# FMC_Power_Module.net
KiCad netlist of a schematic drawn in Altium Designer
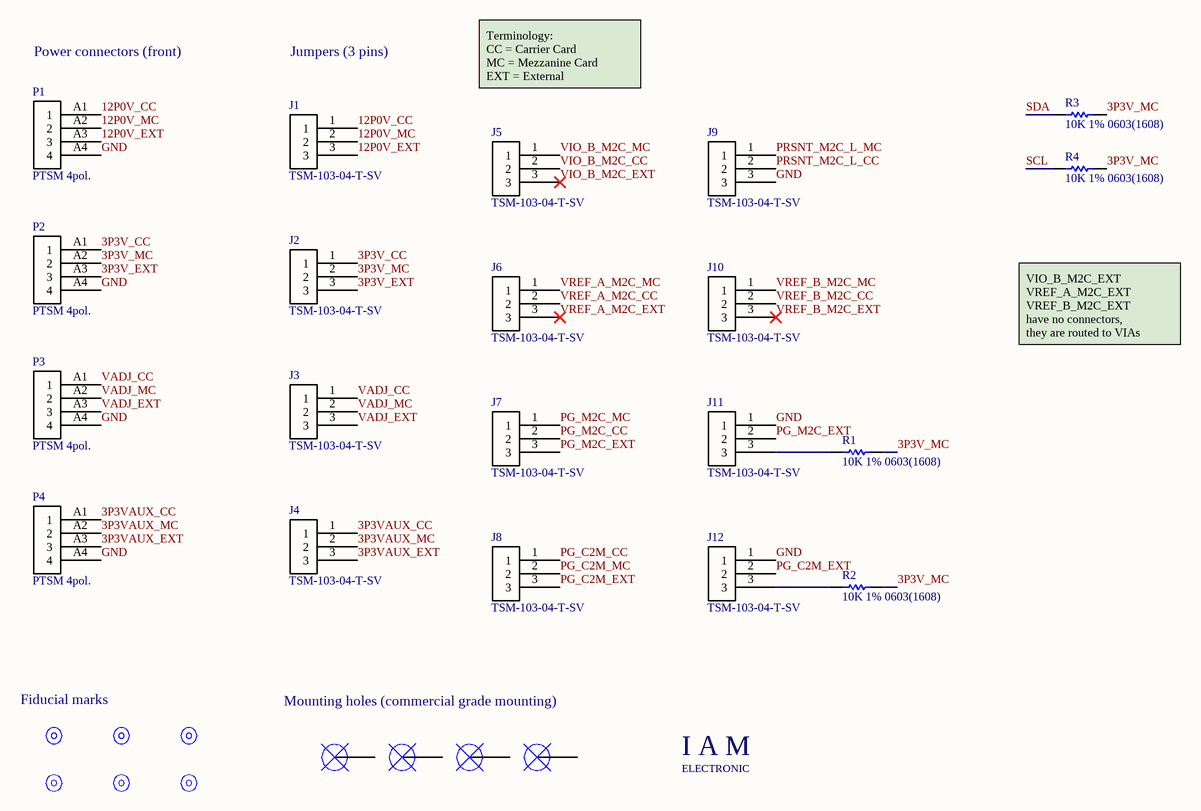
[diagram p0: FMC_Power_Module.SchDoc]

(export (version "E")
  (design (tool "Eeschema 10.0.6"))
  (components
    (comp (ref "FM1")
      (value "1mm")
      (footprint "FIDUCIAL_MARK_ROUND_RING")
      (description "Fiducial mark, width 1mm, clearance 3mm")
      (libsource (lib "VITA_57_FMC") (part "Fiducial_Mark"))
    )
    (comp (ref "FM2")
      (value "1mm")
      (footprint "FIDUCIAL_MARK_ROUND_RING")
      (description "Fiducial mark, width 1mm, clearance 3mm")
      (libsource (lib "VITA_57_FMC") (part "Fiducial_Mark"))
    )
    (comp (ref "FM3")
      (value "1mm")
      (footprint "FIDUCIAL_MARK_ROUND_RING")
      (description "Fiducial mark, width 1mm, clearance 3mm")
      (libsource (lib "VITA_57_FMC") (part "Fiducial_Mark"))
    )
    (comp (ref "FM4")
      (value "1mm")
      (footprint "FIDUCIAL_MARK_ROUND_RING")
      (description "Fiducial mark, width 1mm, clearance 3mm")
      (libsource (lib "VITA_57_FMC") (part "Fiducial_Mark"))
    )
    (comp (ref "FM5")
      (value "1mm")
      (footprint "FIDUCIAL_MARK_ROUND_RING")
      (description "Fiducial mark, width 1mm, clearance 3mm")
      (libsource (lib "VITA_57_FMC") (part "Fiducial_Mark"))
    )
    (comp (ref "FM6")
      (value "1mm")
      (footprint "FIDUCIAL_MARK_ROUND_RING")
      (description "Fiducial mark, width 1mm, clearance 3mm")
      (libsource (lib "VITA_57_FMC") (part "Fiducial_Mark"))
    )
    (comp (ref "J1")
      (value "TSM-103-04-T-SV")
      (footprint "TSM-103-04-T-SV")
      (description ".100\" (2.54 mm) pitch 3 pin header, 0.27\" (6.86 mm) total height, SMT")
      (fields (field (name "MANUFACTURER") "Samtec"))
      (libsource (lib "SMTC-TSM") (part "TSM-103-04-T-SV"))
    )
    (comp (ref "J2")
      (value "TSM-103-04-T-SV")
      (footprint "TSM-103-04-T-SV")
      (description ".100\" (2.54 mm) pitch 3 pin header, 0.27\" (6.86 mm) total height, SMT")
      (fields (field (name "MANUFACTURER") "Samtec"))
      (libsource (lib "SMTC-TSM") (part "TSM-103-04-T-SV"))
    )
    (comp (ref "J3")
      (value "TSM-103-04-T-SV")
      (footprint "TSM-103-04-T-SV")
      (description ".100\" (2.54 mm) pitch 3 pin header, 0.27\" (6.86 mm) total height, SMT")
      (fields (field (name "MANUFACTURER") "Samtec"))
      (libsource (lib "SMTC-TSM") (part "TSM-103-04-T-SV"))
    )
    (comp (ref "J4")
      (value "TSM-103-04-T-SV")
      (footprint "TSM-103-04-T-SV")
      (description ".100\" (2.54 mm) pitch 3 pin header, 0.27\" (6.86 mm) total height, SMT")
      (fields (field (name "MANUFACTURER") "Samtec"))
      (libsource (lib "SMTC-TSM") (part "TSM-103-04-T-SV"))
    )
    (comp (ref "J5")
      (value "TSM-103-04-T-SV")
      (footprint "TSM-103-04-T-SV")
      (description ".100\" (2.54 mm) pitch 3 pin header, 0.27\" (6.86 mm) total height, SMT")
      (fields (field (name "MANUFACTURER") "Samtec"))
      (libsource (lib "SMTC-TSM") (part "TSM-103-04-T-SV"))
    )
    (comp (ref "J6")
      (value "TSM-103-04-T-SV")
      (footprint "TSM-103-04-T-SV")
      (description ".100\" (2.54 mm) pitch 3 pin header, 0.27\" (6.86 mm) total height, SMT")
      (fields (field (name "MANUFACTURER") "Samtec"))
      (libsource (lib "SMTC-TSM") (part "TSM-103-04-T-SV"))
    )
    (comp (ref "J7")
      (value "TSM-103-04-T-SV")
      (footprint "TSM-103-04-T-SV")
      (description ".100\" (2.54 mm) pitch 3 pin header, 0.27\" (6.86 mm) total height, SMT")
      (fields (field (name "MANUFACTURER") "Samtec"))
      (libsource (lib "SMTC-TSM") (part "TSM-103-04-T-SV"))
    )
    (comp (ref "J8")
      (value "TSM-103-04-T-SV")
      (footprint "TSM-103-04-T-SV")
      (description ".100\" (2.54 mm) pitch 3 pin header, 0.27\" (6.86 mm) total height, SMT")
      (fields (field (name "MANUFACTURER") "Samtec"))
      (libsource (lib "SMTC-TSM") (part "TSM-103-04-T-SV"))
    )
    (comp (ref "J9")
      (value "TSM-103-04-T-SV")
      (footprint "TSM-103-04-T-SV")
      (description ".100\" (2.54 mm) pitch 3 pin header, 0.27\" (6.86 mm) total height, SMT")
      (fields (field (name "MANUFACTURER") "Samtec"))
      (libsource (lib "SMTC-TSM") (part "TSM-103-04-T-SV"))
    )
    (comp (ref "J10")
      (value "TSM-103-04-T-SV")
      (footprint "TSM-103-04-T-SV")
      (description ".100\" (2.54 mm) pitch 3 pin header, 0.27\" (6.86 mm) total height, SMT")
      (fields (field (name "MANUFACTURER") "Samtec"))
      (libsource (lib "SMTC-TSM") (part "TSM-103-04-T-SV"))
    )
    (comp (ref "J11")
      (value "TSM-103-04-T-SV")
      (footprint "TSM-103-04-T-SV")
      (description ".100\" (2.54 mm) pitch 3 pin header, 0.27\" (6.86 mm) total height, SMT")
      (fields (field (name "MANUFACTURER") "Samtec"))
      (libsource (lib "SMTC-TSM") (part "TSM-103-04-T-SV"))
    )
    (comp (ref "J12")
      (value "TSM-103-04-T-SV")
      (footprint "TSM-103-04-T-SV")
      (description ".100\" (2.54 mm) pitch 3 pin header, 0.27\" (6.86 mm) total height, SMT")
      (fields (field (name "MANUFACTURER") "Samtec"))
      (libsource (lib "SMTC-TSM") (part "TSM-103-04-T-SV"))
    )
    (comp (ref "MH1")
      (value "2.2mm")
      (footprint "Mounting_Hole_2.2mm")
      (description "Mounting hole, hole size 2.2mm")
      (libsource (lib "VITA_57_FMC") (part "Mounting_Hole_2.2mm"))
    )
    (comp (ref "MH2")
      (value "2.2mm")
      (footprint "Mounting_Hole_2.2mm")
      (description "Mounting hole, hole size 2.2mm")
      (libsource (lib "VITA_57_FMC") (part "Mounting_Hole_2.2mm"))
    )
    (comp (ref "MH3")
      (value "2.7mm")
      (footprint "Mounting_Hole_Plated_2.7mm-COVERED")
      (description "Mounting hole, hole size 2.7mm")
      (libsource (lib "VITA_57_FMC") (part "Mounting_Hole_2.7mm"))
    )
    (comp (ref "MH4")
      (value "2.7mm")
      (footprint "Mounting_Hole_Plated_2.7mm-COVERED")
      (description "Mounting hole, hole size 2.7mm")
      (libsource (lib "VITA_57_FMC") (part "Mounting_Hole_2.7mm"))
    )
    (comp (ref "P1")
      (value "PTSM 4pol.")
      (footprint "PTSM-4pol")
      (description "Phoenix Contact PTSM SMT connector")
      (fields (field (name "MANUFACTURER") "Phoenix Contact") (field (name "PART") "1814650"))
      (libsource (lib "PC-PTSM") (part "PC-PTSM-4pol"))
    )
    (comp (ref "P2")
      (value "PTSM 4pol.")
      (footprint "PTSM-4pol")
      (description "Phoenix Contact PTSM SMT connector")
      (fields (field (name "MANUFACTURER") "Phoenix Contact") (field (name "PART") "1814650"))
      (libsource (lib "PC-PTSM") (part "PC-PTSM-4pol"))
    )
    (comp (ref "P3")
      (value "PTSM 4pol.")
      (footprint "PTSM-4pol")
      (description "Phoenix Contact PTSM SMT connector")
      (fields (field (name "MANUFACTURER") "Phoenix Contact") (field (name "PART") "1814650"))
      (libsource (lib "PC-PTSM") (part "PC-PTSM-4pol"))
    )
    (comp (ref "P4")
      (value "PTSM 4pol.")
      (footprint "PTSM-4pol")
      (description "Phoenix Contact PTSM SMT connector")
      (fields (field (name "MANUFACTURER") "Phoenix Contact") (field (name "PART") "1814650"))
      (libsource (lib "PC-PTSM") (part "PC-PTSM-4pol"))
    )
    (comp (ref "R1")
      (value "10K 1% 0603(1608)")
      (footprint "RESC0603(1608)_N")
      (description "10K 0603 (1608 Metric)  SMD")
      (fields (field (name "POWER") "0.1 W") (field (name "TOLERANCE") "1 %"))
      (libsource (lib "Altium Content Vault") (part "RES"))
    )
    (comp (ref "R2")
      (value "10K 1% 0603(1608)")
      (footprint "RESC0603(1608)_N")
      (description "10K 0603 (1608 Metric)  SMD")
      (fields (field (name "POWER") "0.1 W") (field (name "TOLERANCE") "1 %"))
      (libsource (lib "Altium Content Vault") (part "RES"))
    )
    (comp (ref "R3")
      (value "10K 1% 0603(1608)")
      (footprint "RESC0603(1608)_N")
      (description "10K 0603 (1608 Metric)  SMD")
      (fields (field (name "POWER") "0.1 W") (field (name "TOLERANCE") "1 %"))
      (libsource (lib "Altium Content Vault") (part "RES"))
    )
    (comp (ref "R4")
      (value "10K 1% 0603(1608)")
      (footprint "RESC0603(1608)_N")
      (description "10K 0603 (1608 Metric)  SMD")
      (fields (field (name "POWER") "0.1 W") (field (name "TOLERANCE") "1 %"))
      (libsource (lib "Altium Content Vault") (part "RES"))
    )
    (comp (ref "STR1")
      (value "IAM LOGO")
      (footprint "IAM LOGO - LARGE - WWW")
      (description "I A M E L E C T R O N I C - Logo")
      (fields (field (name "MANUFACTURER") "IAM ELECTRONIC") (field (name "PART") "Logo"))
      (libsource (lib "IAM_LOGOS") (part "IAM_LOGO"))
    )
  )
  (nets
    (net (code "1") (name "/3P3VAUX_CC") (class "Default")
      (node (ref "J4") (pin "1") (pinfunction "1_1") (pintype "passive"))
      (node (ref "P4") (pin "A1") (pinfunction "1_A1") (pintype "passive"))
    )
    (net (code "2") (name "/3P3VAUX_EXT") (class "Default")
      (node (ref "J4") (pin "3") (pinfunction "3_3") (pintype "passive"))
      (node (ref "P4") (pin "A3") (pinfunction "3_A3") (pintype "passive"))
    )
    (net (code "3") (name "/3P3VAUX_MC") (class "Default")
      (node (ref "J4") (pin "2") (pinfunction "2_2") (pintype "passive"))
      (node (ref "P4") (pin "A2") (pinfunction "2_A2") (pintype "passive"))
    )
    (net (code "4") (name "/3P3V_CC") (class "Default")
      (node (ref "J2") (pin "1") (pinfunction "1_1") (pintype "passive"))
      (node (ref "P2") (pin "A1") (pinfunction "1_A1") (pintype "passive"))
    )
    (net (code "5") (name "/3P3V_EXT") (class "Default")
      (node (ref "J2") (pin "3") (pinfunction "3_3") (pintype "passive"))
      (node (ref "P2") (pin "A3") (pinfunction "3_A3") (pintype "passive"))
    )
    (net (code "6") (name "/3P3V_MC") (class "Default")
      (node (ref "J2") (pin "2") (pinfunction "2_2") (pintype "passive"))
      (node (ref "P2") (pin "A2") (pinfunction "2_A2") (pintype "passive"))
      (node (ref "R1") (pin "2") (pinfunction "2_2") (pintype "passive"))
      (node (ref "R2") (pin "2") (pinfunction "2_2") (pintype "passive"))
      (node (ref "R3") (pin "2") (pinfunction "2_2") (pintype "passive"))
      (node (ref "R4") (pin "2") (pinfunction "2_2") (pintype "passive"))
    )
    (net (code "7") (name "/12P0V_CC") (class "Default")
      (node (ref "J1") (pin "1") (pinfunction "1_1") (pintype "passive"))
      (node (ref "P1") (pin "A1") (pinfunction "1_A1") (pintype "passive"))
    )
    (net (code "8") (name "/12P0V_EXT") (class "Default")
      (node (ref "J1") (pin "3") (pinfunction "3_3") (pintype "passive"))
      (node (ref "P1") (pin "A3") (pinfunction "3_A3") (pintype "passive"))
    )
    (net (code "9") (name "/12P0V_MC") (class "Default")
      (node (ref "J1") (pin "2") (pinfunction "2_2") (pintype "passive"))
      (node (ref "P1") (pin "A2") (pinfunction "2_A2") (pintype "passive"))
    )
    (net (code "10") (name "/GND") (class "Default")
      (node (ref "J11") (pin "1") (pinfunction "1_1") (pintype "passive"))
      (node (ref "J12") (pin "1") (pinfunction "1_1") (pintype "passive"))
      (node (ref "J9") (pin "3") (pinfunction "3_3") (pintype "passive"))
      (node (ref "P1") (pin "A4") (pinfunction "4_A4") (pintype "passive"))
      (node (ref "P2") (pin "A4") (pinfunction "4_A4") (pintype "passive"))
      (node (ref "P3") (pin "A4") (pinfunction "4_A4") (pintype "passive"))
      (node (ref "P4") (pin "A4") (pinfunction "4_A4") (pintype "passive"))
    )
    (net (code "11") (name "/PG_C2M_CC") (class "Default")
      (node (ref "J8") (pin "1") (pinfunction "1_1") (pintype "passive"))
    )
    (net (code "12") (name "/PG_C2M_EXT") (class "Default")
      (node (ref "J12") (pin "2") (pinfunction "2_2") (pintype "passive"))
      (node (ref "J8") (pin "3") (pinfunction "3_3") (pintype "passive"))
    )
    (net (code "13") (name "/PG_C2M_MC") (class "Default")
      (node (ref "J8") (pin "2") (pinfunction "2_2") (pintype "passive"))
    )
    (net (code "14") (name "/PG_M2C_CC") (class "Default")
      (node (ref "J7") (pin "2") (pinfunction "2_2") (pintype "passive"))
    )
    (net (code "15") (name "/PG_M2C_EXT") (class "Default")
      (node (ref "J11") (pin "2") (pinfunction "2_2") (pintype "passive"))
      (node (ref "J7") (pin "3") (pinfunction "3_3") (pintype "passive"))
    )
    (net (code "16") (name "/PG_M2C_MC") (class "Default")
      (node (ref "J7") (pin "1") (pinfunction "1_1") (pintype "passive"))
    )
    (net (code "17") (name "/PRSNT_M2C_L_CC") (class "Default")
      (node (ref "J9") (pin "2") (pinfunction "2_2") (pintype "passive"))
    )
    (net (code "18") (name "/PRSNT_M2C_L_MC") (class "Default")
      (node (ref "J9") (pin "1") (pinfunction "1_1") (pintype "passive"))
    )
    (net (code "19") (name "/SCL") (class "Default")
      (node (ref "R4") (pin "1") (pinfunction "1_1") (pintype "passive"))
    )
    (net (code "20") (name "/SDA") (class "Default")
      (node (ref "R3") (pin "1") (pinfunction "1_1") (pintype "passive"))
    )
    (net (code "21") (name "/VADJ_CC") (class "Default")
      (node (ref "J3") (pin "1") (pinfunction "1_1") (pintype "passive"))
      (node (ref "P3") (pin "A1") (pinfunction "1_A1") (pintype "passive"))
    )
    (net (code "22") (name "/VADJ_EXT") (class "Default")
      (node (ref "J3") (pin "3") (pinfunction "3_3") (pintype "passive"))
      (node (ref "P3") (pin "A3") (pinfunction "3_A3") (pintype "passive"))
    )
    (net (code "23") (name "/VADJ_MC") (class "Default")
      (node (ref "J3") (pin "2") (pinfunction "2_2") (pintype "passive"))
      (node (ref "P3") (pin "A2") (pinfunction "2_A2") (pintype "passive"))
    )
    (net (code "24") (name "/VIO_B_M2C_CC") (class "Default")
      (node (ref "J5") (pin "2") (pinfunction "2_2") (pintype "passive"))
    )
    (net (code "25") (name "/VIO_B_M2C_EXT") (class "Default")
      (node (ref "J5") (pin "3") (pinfunction "3_3") (pintype "passive+no_connect"))
    )
    (net (code "26") (name "/VIO_B_M2C_MC") (class "Default")
      (node (ref "J5") (pin "1") (pinfunction "1_1") (pintype "passive"))
    )
    (net (code "27") (name "/VREF_A_M2C_CC") (class "Default")
      (node (ref "J6") (pin "2") (pinfunction "2_2") (pintype "passive"))
    )
    (net (code "28") (name "/VREF_A_M2C_EXT") (class "Default")
      (node (ref "J6") (pin "3") (pinfunction "3_3") (pintype "passive+no_connect"))
    )
    (net (code "29") (name "/VREF_A_M2C_MC") (class "Default")
      (node (ref "J6") (pin "1") (pinfunction "1_1") (pintype "passive"))
    )
    (net (code "30") (name "/VREF_B_M2C_CC") (class "Default")
      (node (ref "J10") (pin "2") (pinfunction "2_2") (pintype "passive"))
    )
    (net (code "31") (name "/VREF_B_M2C_EXT") (class "Default")
      (node (ref "J10") (pin "3") (pinfunction "3_3") (pintype "passive+no_connect"))
    )
    (net (code "32") (name "/VREF_B_M2C_MC") (class "Default")
      (node (ref "J10") (pin "1") (pinfunction "1_1") (pintype "passive"))
    )
    (net (code "33") (name "Net-(J11-Pad3)") (class "Default")
      (node (ref "J11") (pin "3") (pinfunction "3_3") (pintype "passive"))
      (node (ref "R1") (pin "1") (pinfunction "1_1") (pintype "passive"))
    )
    (net (code "34") (name "Net-(J12-Pad3)") (class "Default")
      (node (ref "J12") (pin "3") (pinfunction "3_3") (pintype "passive"))
      (node (ref "R2") (pin "1") (pinfunction "1_1") (pintype "passive"))
    )
    (net (code "35") (name "unconnected-(FM1-PadFD0)") (class "Default")
      (node (ref "FM1") (pin "FD0") (pinfunction "FD0_FD0") (pintype "passive"))
    )
    (net (code "36") (name "unconnected-(FM2-PadFD0)") (class "Default")
      (node (ref "FM2") (pin "FD0") (pinfunction "FD0_FD0") (pintype "passive"))
    )
    (net (code "37") (name "unconnected-(FM3-PadFD0)") (class "Default")
      (node (ref "FM3") (pin "FD0") (pinfunction "FD0_FD0") (pintype "passive"))
    )
    (net (code "38") (name "unconnected-(FM4-PadFD0)") (class "Default")
      (node (ref "FM4") (pin "FD0") (pinfunction "FD0_FD0") (pintype "passive"))
    )
    (net (code "39") (name "unconnected-(FM5-PadFD0)") (class "Default")
      (node (ref "FM5") (pin "FD0") (pinfunction "FD0_FD0") (pintype "passive"))
    )
    (net (code "40") (name "unconnected-(FM6-PadFD0)") (class "Default")
      (node (ref "FM6") (pin "FD0") (pinfunction "FD0_FD0") (pintype "passive"))
    )
    (net (code "41") (name "unconnected-(MH1-Pad0)") (class "Default")
      (node (ref "MH1") (pin "0") (pinfunction "0_0") (pintype "passive"))
    )
    (net (code "42") (name "unconnected-(MH2-Pad0)") (class "Default")
      (node (ref "MH2") (pin "0") (pinfunction "0_0") (pintype "passive"))
    )
    (net (code "43") (name "unconnected-(MH3-Pad0)") (class "Default")
      (node (ref "MH3") (pin "0") (pinfunction "0_0") (pintype "passive"))
    )
    (net (code "44") (name "unconnected-(MH4-Pad0)") (class "Default")
      (node (ref "MH4") (pin "0") (pinfunction "0_0") (pintype "passive"))
    )
  )
)
